# OpenPLCv0_2_0_GPIOExpander.net
KiCad netlist of a schematic drawn in Altium Designer
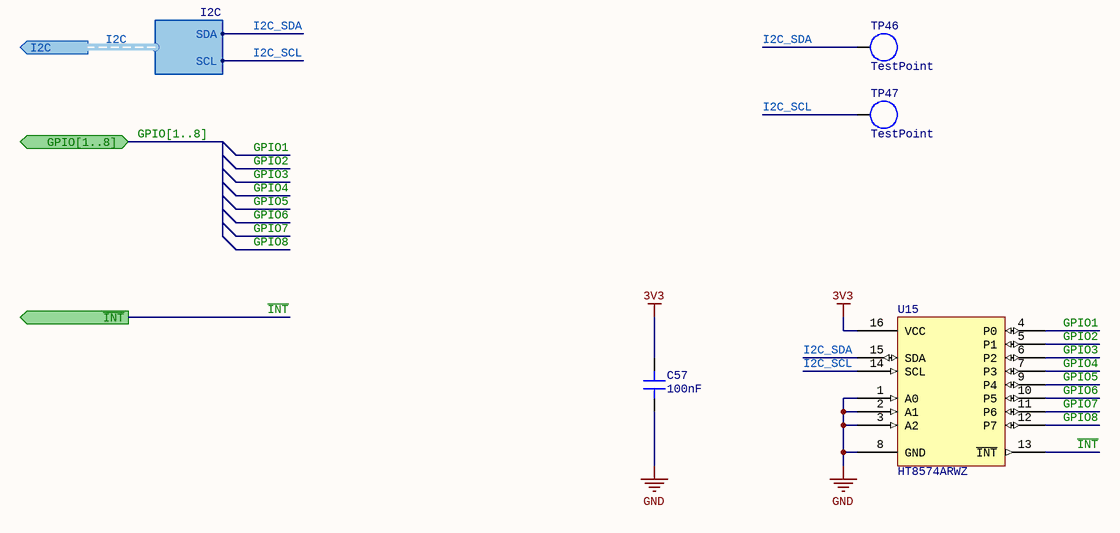
[diagram p0: OpenPLCv0.2.0_GPIOExpander.SchDoc]

(export (version "E")
  (design (tool "Eeschema 10.0.6"))
  (components
    (comp (ref "C57")
      (value "CC0402KRX5R6BB104")
      (footprint "SMD_CAP_0402(1005)_N")
      (description "100nF ±10% 10V X5R 0402 Multilayer Ceramic Capacitors MLCC - SMD/SMT RoHS")
      (fields (field (name "TOLERANCE") "10%") (field (name "CAPACITANCE") "100nF"))
      (libsource (lib "BrauV2_Capacitor") (part "100nF 0402 10V 10%"))
    )
    (comp (ref "TP46")
      (value "TestPoint")
      (footprint "Pad")
      (libsource (lib "OpenPLCv0.2.0_Misc") (part "Test point"))
    )
    (comp (ref "TP47")
      (value "TestPoint")
      (footprint "Pad")
      (libsource (lib "OpenPLCv0.2.0_Misc") (part "Test point"))
    )
    (comp (ref "U15")
      (value "HT8574ARWZ")
      (footprint "TSSOP-16")
      (description "SOP16 Interface - I/O Expanders ROHS (PCF8754 clone)")
      (libsource (lib "BrauV2_IC") (part "HT8574ARWZ"))
    )
  )
  (nets
    (net (code "2") (name "/GPIO1") (class "Default")
      (node (ref "U15") (pin "4") (pinfunction "P0_4") (pintype "bidirectional"))
    )
    (net (code "3") (name "/GPIO2") (class "Default")
      (node (ref "U15") (pin "5") (pinfunction "P1_5") (pintype "bidirectional"))
    )
    (net (code "4") (name "/GPIO3") (class "Default")
      (node (ref "U15") (pin "6") (pinfunction "P2_6") (pintype "bidirectional"))
    )
    (net (code "5") (name "/GPIO4") (class "Default")
      (node (ref "U15") (pin "7") (pinfunction "P3_7") (pintype "bidirectional"))
    )
    (net (code "6") (name "/GPIO5") (class "Default")
      (node (ref "U15") (pin "9") (pinfunction "P4_9") (pintype "bidirectional"))
    )
    (net (code "7") (name "/GPIO6") (class "Default")
      (node (ref "U15") (pin "10") (pinfunction "P5_10") (pintype "bidirectional"))
    )
    (net (code "8") (name "/GPIO7") (class "Default")
      (node (ref "U15") (pin "11") (pinfunction "P6_11") (pintype "bidirectional"))
    )
    (net (code "9") (name "/GPIO8") (class "Default")
      (node (ref "U15") (pin "12") (pinfunction "P7_12") (pintype "bidirectional"))
    )
    (net (code "11") (name "/I2C_SCL") (class "Default")
      (node (ref "TP47") (pin "1") (pinfunction "1_1") (pintype "passive"))
      (node (ref "U15") (pin "14") (pinfunction "SCL_14") (pintype "input"))
    )
    (net (code "12") (name "/I2C_SDA") (class "Default")
      (node (ref "TP46") (pin "1") (pinfunction "1_1") (pintype "passive"))
      (node (ref "U15") (pin "15") (pinfunction "SDA_15") (pintype "bidirectional"))
    )
    (net (code "14") (name "/~{INT}") (class "Default")
      (node (ref "U15") (pin "13") (pinfunction "~{INT}_13") (pintype "output"))
    )
    (net (code "15") (name "3V3") (class "Default")
      (node (ref "C57") (pin "2") (pinfunction "2_2") (pintype "passive"))
      (node (ref "U15") (pin "16") (pinfunction "VCC_16") (pintype "power_in"))
    )
    (net (code "16") (name "GND") (class "Default")
      (node (ref "C57") (pin "1") (pinfunction "1_1") (pintype "passive"))
      (node (ref "U15") (pin "1") (pinfunction "A0_1") (pintype "input"))
      (node (ref "U15") (pin "2") (pinfunction "A1_2") (pintype "input"))
      (node (ref "U15") (pin "3") (pinfunction "A2_3") (pintype "input"))
      (node (ref "U15") (pin "8") (pinfunction "GND_8") (pintype "power_in"))
    )
  )
)
